# CellCircuit.net
KiCad netlist of a schematic drawn in Altium Designer
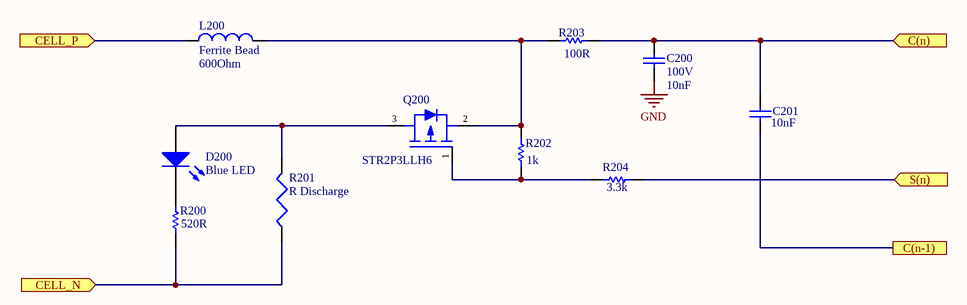
[diagram p0: CellCircuit.SchDoc]

(export (version "E")
  (design (tool "Eeschema 10.0.6"))
  (components
    (comp (ref "C200")
      (value "100V")
      (footprint "RAD-0.3")
      (description "Capacitor")
      (fields (field (name "ALTIUM_VALUE") "10nF") (field (name "PUBLISHER") "Altium Limited"))
      (libsource (lib "Miscellaneous Devices") (part "Cap"))
    )
    (comp (ref "C201")
      (value "10nF")
      (footprint "RAD-0.3")
      (description "Capacitor")
      (fields (field (name "Comment") "C0805") (field (name "PUBLISHER") "Altium Limited"))
      (libsource (lib "Miscellaneous Devices") (part "Cap"))
    )
    (comp (ref "D200")
      (value "Blue LED")
      (footprint "LED-0")
      (description "Typical INFRARED GaAs LED")
      (fields (field (name "PUBLISHER") "Altium Limited"))
      (libsource (lib "Miscellaneous Devices") (part "LED0"))
    )
    (comp (ref "L200")
      (value "Ferrite Bead")
      (footprint "0402-A")
      (description "Inductor Coil - Ferrite Bead")
      (fields (field (name "ALTIUM_VALUE") "600Ohm") (field (name "PUBLISHER") "Altium Limited"))
      (libsource (lib "Miscellaneous Devices") (part "Inductor"))
    )
    (comp (ref "Q200")
      (value "STR2P3LLH6")
      (footprint "SOT95P280X110-3N")
      (description "P-channel -30 V, 48 mΩ typICAL, -2 A STripFET™ H6 Power MOSFET in a SOT-23 package.")
      (libsource (lib "STR2P3LLH6") (part "STR2P3LLH6"))
    )
    (comp (ref "R200")
      (value "520R")
      (footprint "AXIAL-0.3")
      (description "Resistor")
      (fields (field (name "Comment") "R0805") (field (name "PUBLISHER") "Altium Limited"))
      (libsource (lib "Miscellaneous Devices") (part "Res1"))
    )
    (comp (ref "R201")
      (value "R Discharge")
      (description "Discharge Resistance")
      (libsource (lib "R-Discharge") (part "R Discharge"))
    )
    (comp (ref "R202")
      (value "1k")
      (footprint "AXIAL-0.3")
      (description "Resistor")
      (fields (field (name "Comment") "R0805") (field (name "PUBLISHER") "Altium Limited"))
      (libsource (lib "Miscellaneous Devices") (part "Res1"))
    )
    (comp (ref "R203")
      (value "100R")
      (footprint "AXIAL-0.3")
      (description "Resistor")
      (fields (field (name "Comment") "R0805") (field (name "PUBLISHER") "Altium Limited"))
      (libsource (lib "Miscellaneous Devices") (part "Res1"))
    )
    (comp (ref "R204")
      (value "3.3k")
      (footprint "AXIAL-0.3")
      (description "Resistor")
      (fields (field (name "Comment") "R0805") (field (name "PUBLISHER") "Altium Limited"))
      (libsource (lib "Miscellaneous Devices") (part "Res1"))
    )
  )
  (nets
    (net (code "1") (name "/C(n)") (class "Default")
      (node (ref "C200") (pin "1") (pinfunction "1_1") (pintype "passive"))
      (node (ref "C201") (pin "1") (pinfunction "1_1") (pintype "passive"))
      (node (ref "R203") (pin "1") (pinfunction "1_1") (pintype "passive"))
    )
    (net (code "2") (name "/C(n-1)") (class "Default")
      (node (ref "C201") (pin "2") (pinfunction "2_2") (pintype "passive"))
    )
    (net (code "3") (name "/CELL_N") (class "Default")
      (node (ref "R200") (pin "1") (pinfunction "1_1") (pintype "passive"))
      (node (ref "R201") (pin "1") (pinfunction "1_1") (pintype "passive"))
    )
    (net (code "4") (name "/CELL_P") (class "Default")
      (node (ref "L200") (pin "1") (pinfunction "1_1") (pintype "passive"))
    )
    (net (code "5") (name "/S(n)") (class "Default")
      (node (ref "R204") (pin "1") (pinfunction "1_1") (pintype "passive"))
    )
    (net (code "6") (name "GND") (class "Default")
      (node (ref "C200") (pin "2") (pinfunction "2_2") (pintype "passive"))
    )
    (net (code "7") (name "Net-(D200-A)") (class "Default")
      (node (ref "D200") (pin "1") (pinfunction "A_1") (pintype "passive"))
      (node (ref "Q200") (pin "3") (pinfunction "3_3") (pintype "passive"))
      (node (ref "R201") (pin "2") (pinfunction "2_2") (pintype "passive"))
    )
    (net (code "8") (name "Net-(D200-K)") (class "Default")
      (node (ref "D200") (pin "2") (pinfunction "K_2") (pintype "passive"))
      (node (ref "R200") (pin "2") (pinfunction "2_2") (pintype "passive"))
    )
    (net (code "9") (name "Net-(L200-Pad2)") (class "Default")
      (node (ref "L200") (pin "2") (pinfunction "2_2") (pintype "passive"))
      (node (ref "Q200") (pin "2") (pinfunction "2_2") (pintype "passive"))
      (node (ref "R202") (pin "2") (pinfunction "2_2") (pintype "passive"))
      (node (ref "R203") (pin "2") (pinfunction "2_2") (pintype "passive"))
    )
    (net (code "10") (name "Net-(Q200-Pad1)") (class "Default")
      (node (ref "Q200") (pin "1") (pinfunction "1_1") (pintype "passive"))
      (node (ref "R202") (pin "1") (pinfunction "1_1") (pintype "passive"))
      (node (ref "R204") (pin "2") (pinfunction "2_2") (pintype "passive"))
    )
  )
)
